# preamplifier.net
KiCad netlist of a schematic drawn in Altium Designer
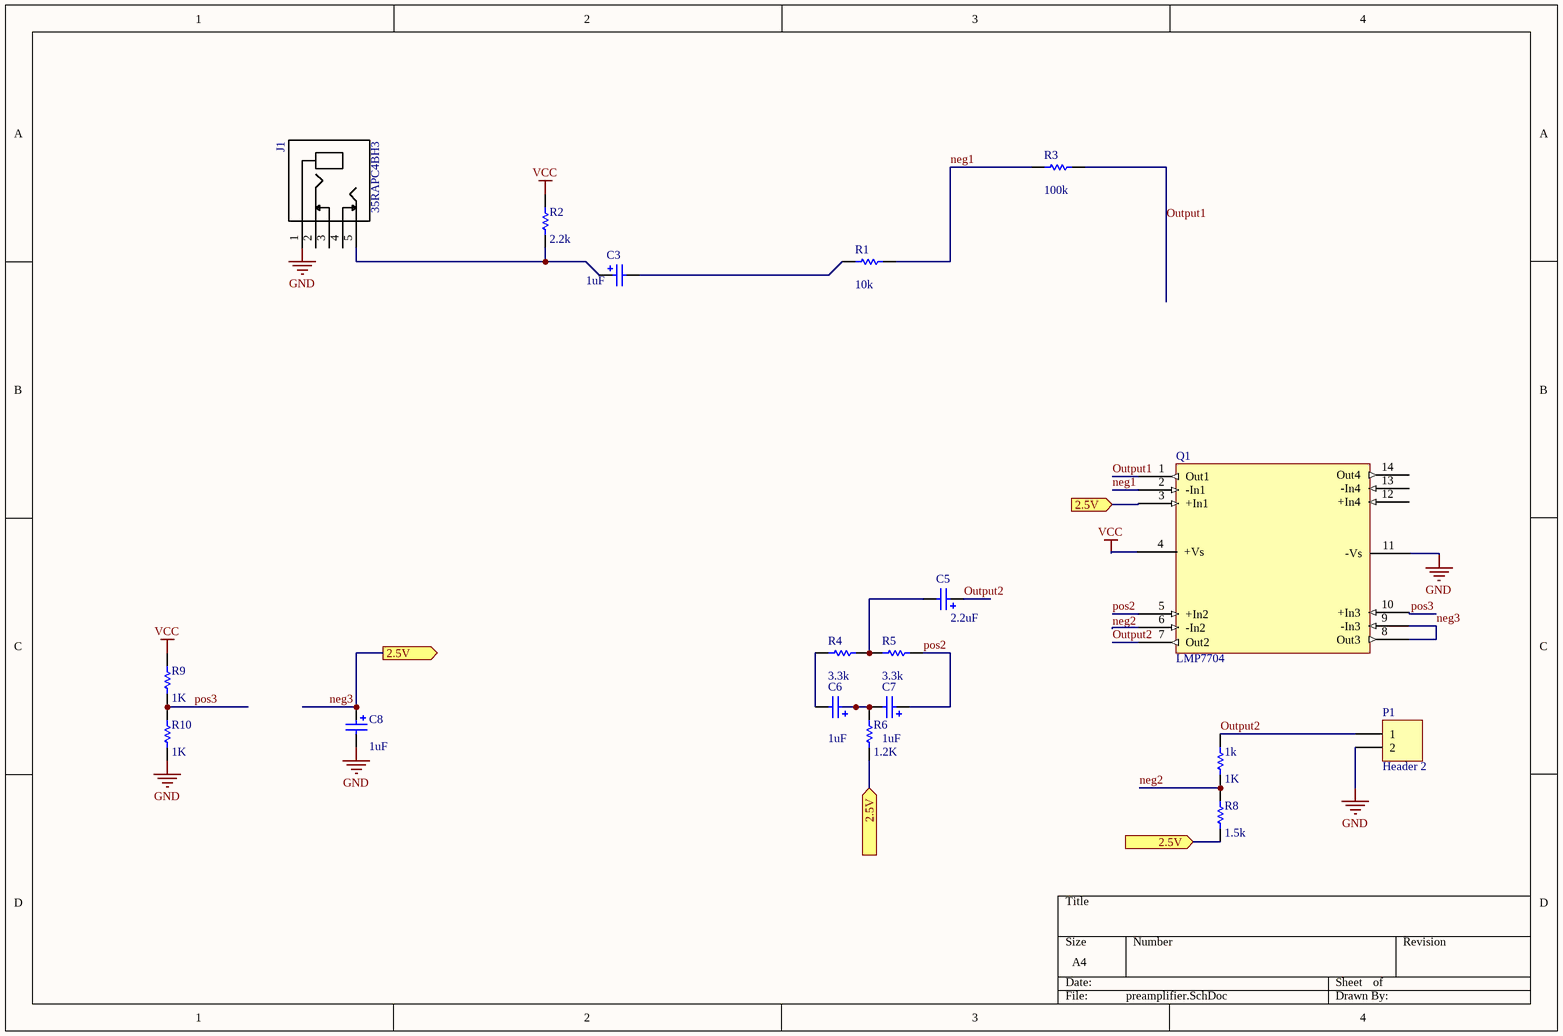
[diagram p0: preamplifier.SchDoc]

(export (version "E")
  (design (tool "Eeschema 10.0.6"))
  (components
    (comp (ref "1k")
      (value "1K")
      (footprint "AXIAL-0.3")
      (description "Resistor")
      (fields (field (name "PUBLISHER") "Altium Limited"))
      (libsource (lib "Miscellaneous Devices") (part "Res1"))
    )
    (comp (ref "C3")
      (value "1uF")
      (footprint "Capacitor 5mmx11mm")
      (description "Polarized Capacitor (Radial)")
      (fields (field (name "PUBLISHER") "Altium Limited"))
      (libsource (lib "Miscellaneous Devices") (part "Cap Pol1"))
    )
    (comp (ref "C5")
      (value "2.2uF")
      (footprint "Capacitor 5mmx11mm")
      (description "Polarized Capacitor (Radial)")
      (fields (field (name "PUBLISHER") "Altium Limited"))
      (libsource (lib "Miscellaneous Devices") (part "Cap Pol1"))
    )
    (comp (ref "C6")
      (value "1uF")
      (footprint "Capacitor 5mmx11mm")
      (description "Polarized Capacitor (Radial)")
      (fields (field (name "PUBLISHER") "Altium Limited"))
      (libsource (lib "Miscellaneous Devices") (part "Cap Pol1"))
    )
    (comp (ref "C7")
      (value "1uF")
      (footprint "Capacitor 5mmx11mm")
      (description "Polarized Capacitor (Radial)")
      (fields (field (name "PUBLISHER") "Altium Limited"))
      (libsource (lib "Miscellaneous Devices") (part "Cap Pol1"))
    )
    (comp (ref "C8")
      (value "1uF")
      (footprint "Capacitor 5mmx11mm")
      (description "Polarized Capacitor (Radial)")
      (fields (field (name "PUBLISHER") "Altium Limited"))
      (libsource (lib "Miscellaneous Devices") (part "Cap Pol1"))
    )
    (comp (ref "J1")
      (value "35RAPC4BH3")
      (footprint "*SWITCHCRAFT_35RAPC4BH3")
      (description "3.50mm _0.141, 1/8, Mini Plug_ - Headphone Phone Jack Stereo _3 Conductor, TRS_ Connector Solder")
      (fields (field (name "MF") "Switchcraft Inc."))
      (libsource (lib "35RAPC4BH3") (part "35RAPC4BH3"))
    )
    (comp (ref "P1")
      (value "Header 2")
      (footprint "HDR1X2")
      (description "Header, 2-Pin")
      (fields (field (name "PUBLISHER") "Altium Limited"))
      (libsource (lib "Miscellaneous Connectors") (part "Header 2"))
    )
    (comp (ref "Q1")
      (value "LMP7704")
      (footprint "SOIC-14_BREAKOUT")
      (libsource (lib "preamp") (part "LMP7704"))
    )
    (comp (ref "R1")
      (value "10k")
      (footprint "AXIAL-0.3")
      (description "Resistor")
      (fields (field (name "PUBLISHER") "Altium Limited"))
      (libsource (lib "Miscellaneous Devices") (part "Res1"))
    )
    (comp (ref "R2")
      (value "2.2k")
      (footprint "AXIAL-0.3")
      (description "Resistor")
      (fields (field (name "PUBLISHER") "Altium Limited"))
      (libsource (lib "Miscellaneous Devices") (part "Res1"))
    )
    (comp (ref "R3")
      (value "100k")
      (footprint "AXIAL-0.3")
      (description "Resistor")
      (fields (field (name "PUBLISHER") "Altium Limited"))
      (libsource (lib "Miscellaneous Devices") (part "Res1"))
    )
    (comp (ref "R4")
      (value "3.3k")
      (footprint "AXIAL-0.3")
      (description "Resistor")
      (fields (field (name "PUBLISHER") "Altium Limited"))
      (libsource (lib "Miscellaneous Devices") (part "Res1"))
    )
    (comp (ref "R5")
      (value "3.3k")
      (footprint "AXIAL-0.3")
      (description "Resistor")
      (fields (field (name "PUBLISHER") "Altium Limited"))
      (libsource (lib "Miscellaneous Devices") (part "Res1"))
    )
    (comp (ref "R6")
      (value "1.2K")
      (footprint "AXIAL-0.3")
      (description "Resistor")
      (fields (field (name "PUBLISHER") "Altium Limited"))
      (libsource (lib "Miscellaneous Devices") (part "Res1"))
    )
    (comp (ref "R8")
      (value "1.5k")
      (footprint "AXIAL-0.3")
      (description "Resistor")
      (fields (field (name "PUBLISHER") "Altium Limited"))
      (libsource (lib "Miscellaneous Devices") (part "Res1"))
    )
    (comp (ref "R9")
      (value "1K")
      (footprint "AXIAL-0.3")
      (description "Resistor")
      (fields (field (name "PUBLISHER") "Altium Limited"))
      (libsource (lib "Miscellaneous Devices") (part "Res1"))
    )
    (comp (ref "R10")
      (value "1K")
      (footprint "AXIAL-0.3")
      (description "Resistor")
      (fields (field (name "PUBLISHER") "Altium Limited"))
      (libsource (lib "Miscellaneous Devices") (part "Res1"))
    )
  )
  (nets
    (net (code "1") (name "/Output1") (class "Default")
      (node (ref "Q1") (pin "1") (pinfunction "Out1_1") (pintype "output"))
      (node (ref "R3") (pin "2") (pinfunction "2_2") (pintype "passive"))
    )
    (net (code "2") (name "/Output2") (class "Default")
      (node (ref "1k") (pin "2") (pinfunction "2_2") (pintype "passive"))
      (node (ref "C5") (pin "1") (pinfunction "1_1") (pintype "passive"))
      (node (ref "P1") (pin "1") (pinfunction "1_1") (pintype "passive"))
      (node (ref "Q1") (pin "7") (pinfunction "Out2_7") (pintype "output"))
    )
    (net (code "3") (name "/neg1") (class "Default")
      (node (ref "Q1") (pin "2") (pinfunction "-In1_2") (pintype "input"))
      (node (ref "R1") (pin "2") (pinfunction "2_2") (pintype "passive"))
      (node (ref "R3") (pin "1") (pinfunction "1_1") (pintype "passive"))
    )
    (net (code "4") (name "/neg2") (class "Default")
      (node (ref "1k") (pin "1") (pinfunction "1_1") (pintype "passive"))
      (node (ref "Q1") (pin "6") (pinfunction "-In2_6") (pintype "input"))
      (node (ref "R8") (pin "1") (pinfunction "1_1") (pintype "passive"))
    )
    (net (code "5") (name "/neg3") (class "Default")
      (node (ref "C8") (pin "1") (pinfunction "1_1") (pintype "passive"))
      (node (ref "Q1") (pin "3") (pinfunction "+In1_3") (pintype "input"))
      (node (ref "Q1") (pin "8") (pinfunction "Out3_8") (pintype "output"))
      (node (ref "Q1") (pin "9") (pinfunction "-In3_9") (pintype "input"))
      (node (ref "R6") (pin "1") (pinfunction "1_1") (pintype "passive"))
      (node (ref "R8") (pin "2") (pinfunction "2_2") (pintype "passive"))
    )
    (net (code "6") (name "/pos2") (class "Default")
      (node (ref "C7") (pin "1") (pinfunction "1_1") (pintype "passive"))
      (node (ref "Q1") (pin "5") (pinfunction "+In2_5") (pintype "input"))
      (node (ref "R5") (pin "2") (pinfunction "2_2") (pintype "passive"))
    )
    (net (code "7") (name "/pos3") (class "Default")
      (node (ref "Q1") (pin "10") (pinfunction "+In3_10") (pintype "input"))
      (node (ref "R10") (pin "2") (pinfunction "2_2") (pintype "passive"))
      (node (ref "R9") (pin "1") (pinfunction "1_1") (pintype "passive"))
    )
    (net (code "8") (name "GND") (class "Default")
      (node (ref "C8") (pin "2") (pinfunction "2_2") (pintype "passive"))
      (node (ref "J1") (pin "1") (pinfunction "1_1") (pintype "passive"))
      (node (ref "P1") (pin "2") (pinfunction "2_2") (pintype "passive"))
      (node (ref "Q1") (pin "11") (pinfunction "-Vs_11") (pintype "power_in"))
      (node (ref "R10") (pin "1") (pinfunction "1_1") (pintype "passive"))
    )
    (net (code "9") (name "Net-(C3-Pad1)") (class "Default")
      (node (ref "C3") (pin "1") (pinfunction "1_1") (pintype "passive"))
      (node (ref "J1") (pin "5") (pinfunction "5_5") (pintype "passive"))
      (node (ref "R2") (pin "1") (pinfunction "1_1") (pintype "passive"))
    )
    (net (code "10") (name "Net-(C3-Pad2)") (class "Default")
      (node (ref "C3") (pin "2") (pinfunction "2_2") (pintype "passive"))
      (node (ref "R1") (pin "1") (pinfunction "1_1") (pintype "passive"))
    )
    (net (code "11") (name "Net-(C5-Pad2)") (class "Default")
      (node (ref "C5") (pin "2") (pinfunction "2_2") (pintype "passive"))
      (node (ref "R4") (pin "2") (pinfunction "2_2") (pintype "passive"))
      (node (ref "R5") (pin "1") (pinfunction "1_1") (pintype "passive"))
    )
    (net (code "12") (name "Net-(C6-Pad1)") (class "Default")
      (node (ref "C6") (pin "1") (pinfunction "1_1") (pintype "passive"))
      (node (ref "C7") (pin "2") (pinfunction "2_2") (pintype "passive"))
      (node (ref "R6") (pin "2") (pinfunction "2_2") (pintype "passive"))
    )
    (net (code "13") (name "Net-(C6-Pad2)") (class "Default")
      (node (ref "C6") (pin "2") (pinfunction "2_2") (pintype "passive"))
      (node (ref "R4") (pin "1") (pinfunction "1_1") (pintype "passive"))
    )
    (net (code "14") (name "VCC") (class "Default")
      (node (ref "Q1") (pin "4") (pinfunction "+Vs_4") (pintype "power_in"))
      (node (ref "R2") (pin "2") (pinfunction "2_2") (pintype "passive"))
      (node (ref "R9") (pin "2") (pinfunction "2_2") (pintype "passive"))
    )
    (net (code "15") (name "unconnected-(J1-Pad2)") (class "Default")
      (node (ref "J1") (pin "2") (pinfunction "2_2") (pintype "passive"))
    )
    (net (code "16") (name "unconnected-(J1-Pad3)") (class "Default")
      (node (ref "J1") (pin "3") (pinfunction "3_3") (pintype "passive"))
    )
    (net (code "17") (name "unconnected-(J1-Pad4)") (class "Default")
      (node (ref "J1") (pin "4") (pinfunction "4_4") (pintype "passive"))
    )
    (net (code "18") (name "unconnected-(Q1-+In4-Pad12)") (class "Default")
      (node (ref "Q1") (pin "12") (pinfunction "+In4_12") (pintype "input"))
    )
    (net (code "19") (name "unconnected-(Q1--In4-Pad13)") (class "Default")
      (node (ref "Q1") (pin "13") (pinfunction "-In4_13") (pintype "input"))
    )
    (net (code "20") (name "unconnected-(Q1-Out4-Pad14)") (class "Default")
      (node (ref "Q1") (pin "14") (pinfunction "Out4_14") (pintype "output"))
    )
  )
)
